# simpleArm-1.net
KiCad netlist of a schematic drawn in EAGLE
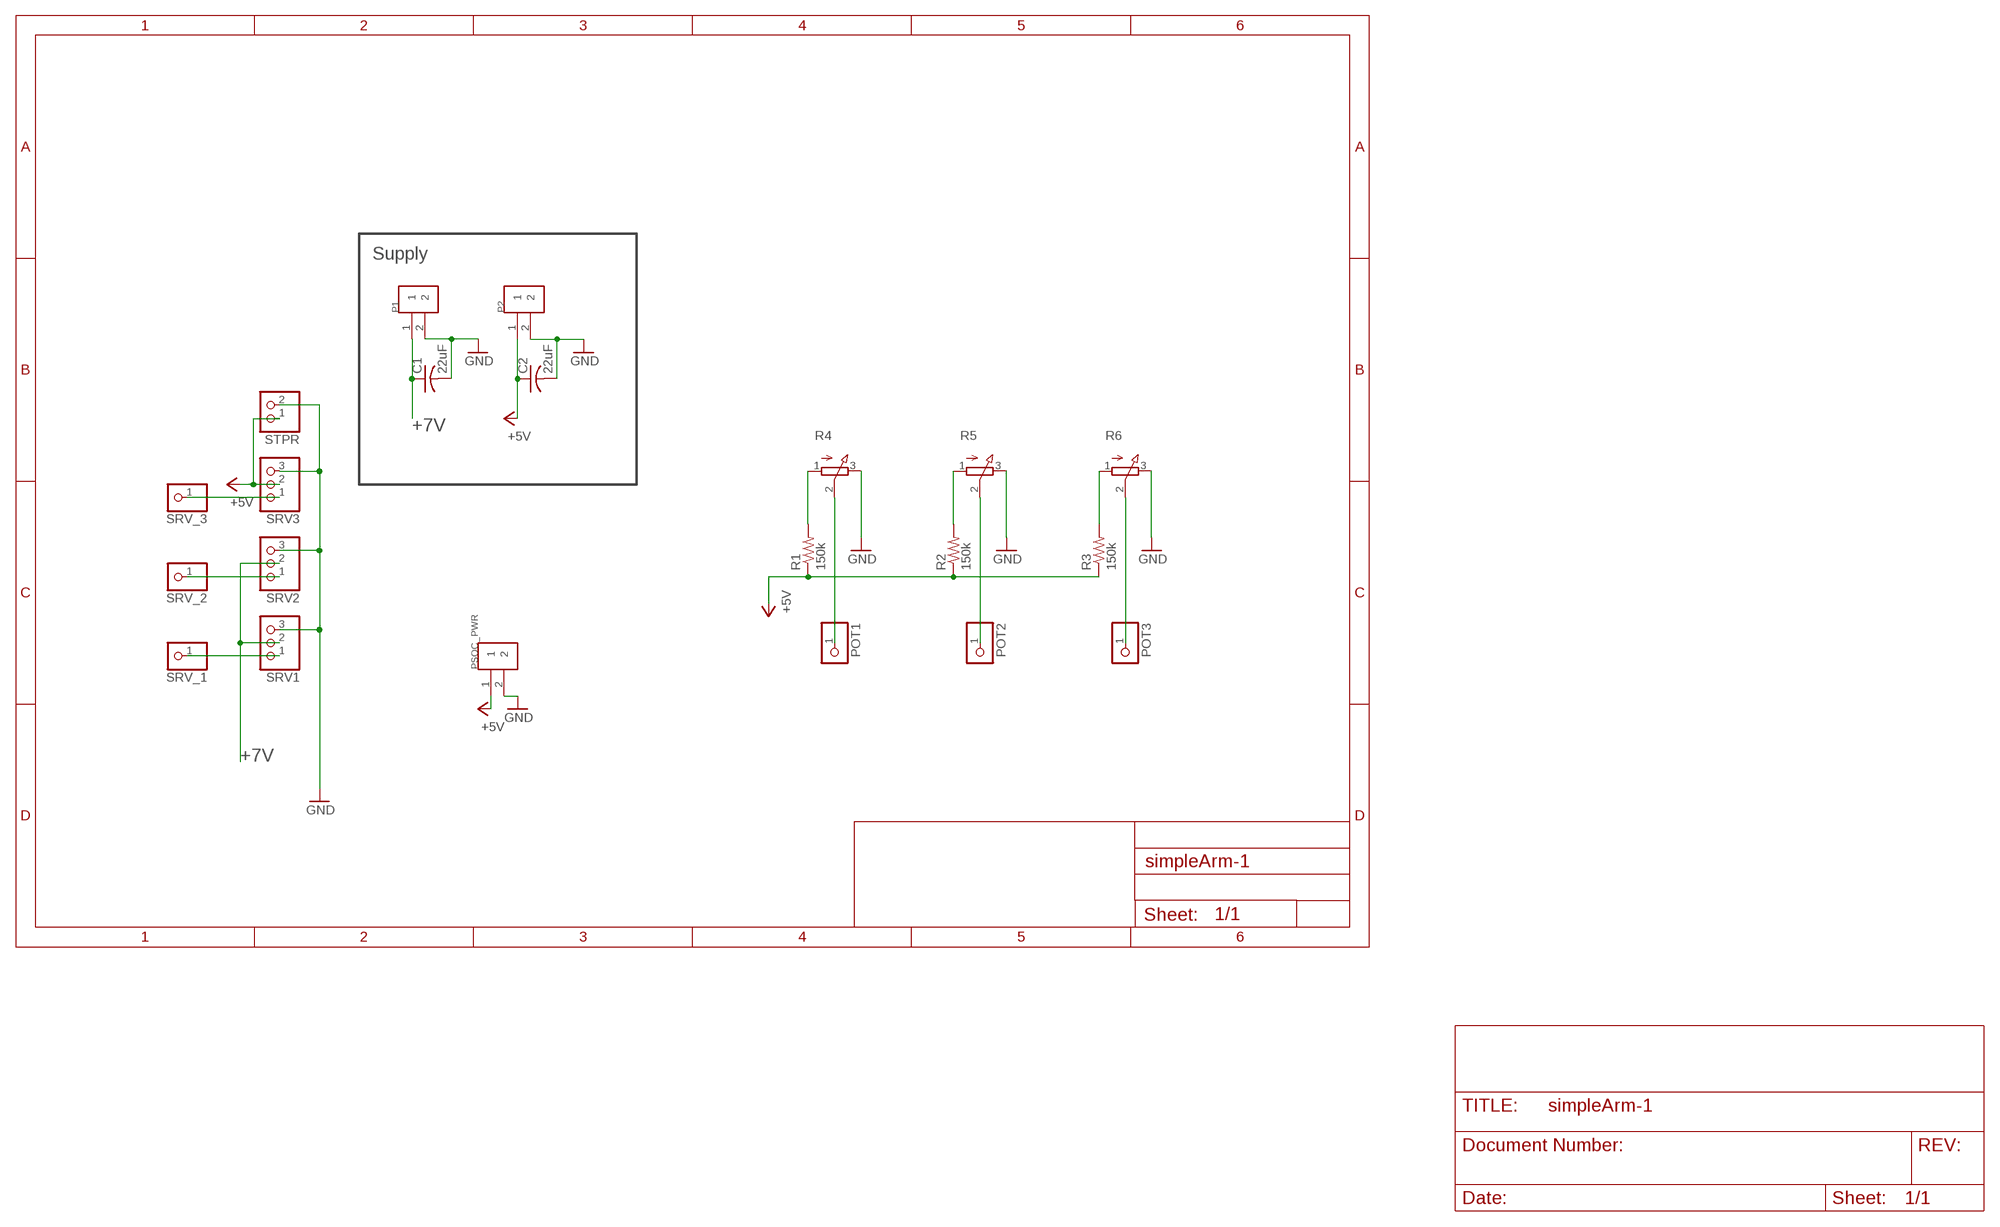
[diagram p0: schematic, sheet 1]

(export (version "E")
  (design (tool "Eeschema 10.0.6"))
  (components
    (comp (ref "C1")
      (value "22uF")
      (footprint "eagle-import:C050-030X075")
      (libsource (lib "eagle-import") (part "C-US050-030X075"))
    )
    (comp (ref "C2")
      (value "22uF")
      (footprint "eagle-import:C050-030X075")
      (libsource (lib "eagle-import") (part "C-US050-030X075"))
    )
    (comp (ref "P1")
      (value "282837-2")
      (footprint "eagle-import:TE_282837-2")
      (fields (field (name "MF") "TE Connectivity"))
      (libsource (lib "eagle-import") (part "282837-2"))
    )
    (comp (ref "P2")
      (value "282837-2")
      (footprint "eagle-import:TE_282837-2")
      (fields (field (name "MF") "TE Connectivity"))
      (libsource (lib "eagle-import") (part "282837-2"))
    )
    (comp (ref "POT1")
      (value "PINHD-1X1")
      (footprint "eagle-import:1X01")
      (libsource (lib "eagle-import") (part "PINHD-1X1"))
    )
    (comp (ref "POT2")
      (value "PINHD-1X1")
      (footprint "eagle-import:1X01")
      (libsource (lib "eagle-import") (part "PINHD-1X1"))
    )
    (comp (ref "POT3")
      (value "PINHD-1X1")
      (footprint "eagle-import:1X01")
      (libsource (lib "eagle-import") (part "PINHD-1X1"))
    )
    (comp (ref "PSOC_PWR")
      (value "282837-2")
      (footprint "eagle-import:TE_282837-2")
      (fields (field (name "MF") "TE Connectivity"))
      (libsource (lib "eagle-import") (part "282837-2"))
    )
    (comp (ref "R1")
      (value "150k")
      (footprint "eagle-import:0204_7")
      (libsource (lib "eagle-import") (part "R-US_0204/7"))
    )
    (comp (ref "R2")
      (value "150k")
      (footprint "eagle-import:0204_7")
      (libsource (lib "eagle-import") (part "R-US_0204/7"))
    )
    (comp (ref "R3")
      (value "150k")
      (footprint "eagle-import:0204_7")
      (libsource (lib "eagle-import") (part "R-US_0204/7"))
    )
    (comp (ref "R4")
      (value "3RP/1610N")
      (footprint "eagle-import:3RP_1610N")
      (libsource (lib "eagle-import") (part "3RP/1610N"))
    )
    (comp (ref "R5")
      (value "3RP/1610N")
      (footprint "eagle-import:3RP_1610N")
      (libsource (lib "eagle-import") (part "3RP/1610N"))
    )
    (comp (ref "R6")
      (value "3RP/1610N")
      (footprint "eagle-import:3RP_1610N")
      (libsource (lib "eagle-import") (part "3RP/1610N"))
    )
    (comp (ref "SRV1")
      (value "PINHD-1X3")
      (footprint "eagle-import:1X03")
      (libsource (lib "eagle-import") (part "PINHD-1X3"))
    )
    (comp (ref "SRV2")
      (value "PINHD-1X3")
      (footprint "eagle-import:1X03")
      (libsource (lib "eagle-import") (part "PINHD-1X3"))
    )
    (comp (ref "SRV3")
      (value "PINHD-1X3")
      (footprint "eagle-import:1X03")
      (libsource (lib "eagle-import") (part "PINHD-1X3"))
    )
    (comp (ref "SRV_1")
      (value "PINHD-1X1")
      (footprint "eagle-import:1X01")
      (libsource (lib "eagle-import") (part "PINHD-1X1"))
    )
    (comp (ref "SRV_2")
      (value "PINHD-1X1")
      (footprint "eagle-import:1X01")
      (libsource (lib "eagle-import") (part "PINHD-1X1"))
    )
    (comp (ref "SRV_3")
      (value "PINHD-1X1")
      (footprint "eagle-import:1X01")
      (libsource (lib "eagle-import") (part "PINHD-1X1"))
    )
    (comp (ref "STPR")
      (value "PINHD-1X2")
      (footprint "eagle-import:1X02")
      (libsource (lib "eagle-import") (part "PINHD-1X2"))
    )
  )
  (nets
    (net (code "1") (name "+5V") (class "Default")
      (node (ref "C2") (pin "1") (pinfunction "1_1") (pintype "passive"))
      (node (ref "P2") (pin "1") (pinfunction "1_1") (pintype "passive"))
      (node (ref "PSOC_PWR") (pin "1") (pinfunction "1_1") (pintype "passive"))
      (node (ref "R1") (pin "1") (pinfunction "1_1") (pintype "passive"))
      (node (ref "R2") (pin "1") (pinfunction "1_1") (pintype "passive"))
      (node (ref "R3") (pin "1") (pinfunction "1_1") (pintype "passive"))
      (node (ref "SRV3") (pin "2") (pinfunction "2_2") (pintype "passive"))
      (node (ref "STPR") (pin "1") (pinfunction "1_1") (pintype "passive"))
    )
    (net (code "2") (name "/+7V") (class "Default")
      (node (ref "C1") (pin "1") (pinfunction "1_1") (pintype "passive"))
      (node (ref "P1") (pin "1") (pinfunction "1_1") (pintype "passive"))
      (node (ref "SRV1") (pin "2") (pinfunction "2_2") (pintype "passive"))
      (node (ref "SRV2") (pin "2") (pinfunction "2_2") (pintype "passive"))
    )
    (net (code "3") (name "GND") (class "Default")
      (node (ref "C1") (pin "2") (pinfunction "2_2") (pintype "passive"))
      (node (ref "C2") (pin "2") (pinfunction "2_2") (pintype "passive"))
      (node (ref "P1") (pin "2") (pinfunction "2_2") (pintype "passive"))
      (node (ref "P2") (pin "2") (pinfunction "2_2") (pintype "passive"))
      (node (ref "PSOC_PWR") (pin "2") (pinfunction "2_2") (pintype "passive"))
      (node (ref "R4") (pin "3") (pinfunction "E_3") (pintype "passive"))
      (node (ref "R5") (pin "3") (pinfunction "E_3") (pintype "passive"))
      (node (ref "R6") (pin "3") (pinfunction "E_3") (pintype "passive"))
      (node (ref "SRV1") (pin "3") (pinfunction "3_3") (pintype "passive"))
      (node (ref "SRV2") (pin "3") (pinfunction "3_3") (pintype "passive"))
      (node (ref "SRV3") (pin "3") (pinfunction "3_3") (pintype "passive"))
      (node (ref "STPR") (pin "2") (pinfunction "2_2") (pintype "passive"))
    )
    (net (code "4") (name "Net-(R4-A)") (class "Default")
      (node (ref "R1") (pin "2") (pinfunction "2_2") (pintype "passive"))
      (node (ref "R4") (pin "1") (pinfunction "A_1") (pintype "passive"))
    )
    (net (code "5") (name "Net-(R4-S)") (class "Default")
      (node (ref "POT1") (pin "1") (pinfunction "1_1") (pintype "passive"))
      (node (ref "R4") (pin "2") (pinfunction "S_2") (pintype "passive"))
    )
    (net (code "6") (name "Net-(R5-A)") (class "Default")
      (node (ref "R2") (pin "2") (pinfunction "2_2") (pintype "passive"))
      (node (ref "R5") (pin "1") (pinfunction "A_1") (pintype "passive"))
    )
    (net (code "7") (name "Net-(R5-S)") (class "Default")
      (node (ref "POT2") (pin "1") (pinfunction "1_1") (pintype "passive"))
      (node (ref "R5") (pin "2") (pinfunction "S_2") (pintype "passive"))
    )
    (net (code "8") (name "Net-(R6-A)") (class "Default")
      (node (ref "R3") (pin "2") (pinfunction "2_2") (pintype "passive"))
      (node (ref "R6") (pin "1") (pinfunction "A_1") (pintype "passive"))
    )
    (net (code "9") (name "Net-(R6-S)") (class "Default")
      (node (ref "POT3") (pin "1") (pinfunction "1_1") (pintype "passive"))
      (node (ref "R6") (pin "2") (pinfunction "S_2") (pintype "passive"))
    )
    (net (code "10") (name "Net-(SRV1-Pad1)") (class "Default")
      (node (ref "SRV1") (pin "1") (pinfunction "1_1") (pintype "passive"))
      (node (ref "SRV_1") (pin "1") (pinfunction "1_1") (pintype "passive"))
    )
    (net (code "11") (name "Net-(SRV2-Pad1)") (class "Default")
      (node (ref "SRV2") (pin "1") (pinfunction "1_1") (pintype "passive"))
      (node (ref "SRV_2") (pin "1") (pinfunction "1_1") (pintype "passive"))
    )
    (net (code "12") (name "Net-(SRV3-Pad1)") (class "Default")
      (node (ref "SRV3") (pin "1") (pinfunction "1_1") (pintype "passive"))
      (node (ref "SRV_3") (pin "1") (pinfunction "1_1") (pintype "passive"))
    )
  )
)
